# Wall_Power_to__-20.net
KiCad netlist of a schematic drawn in Altium Designer
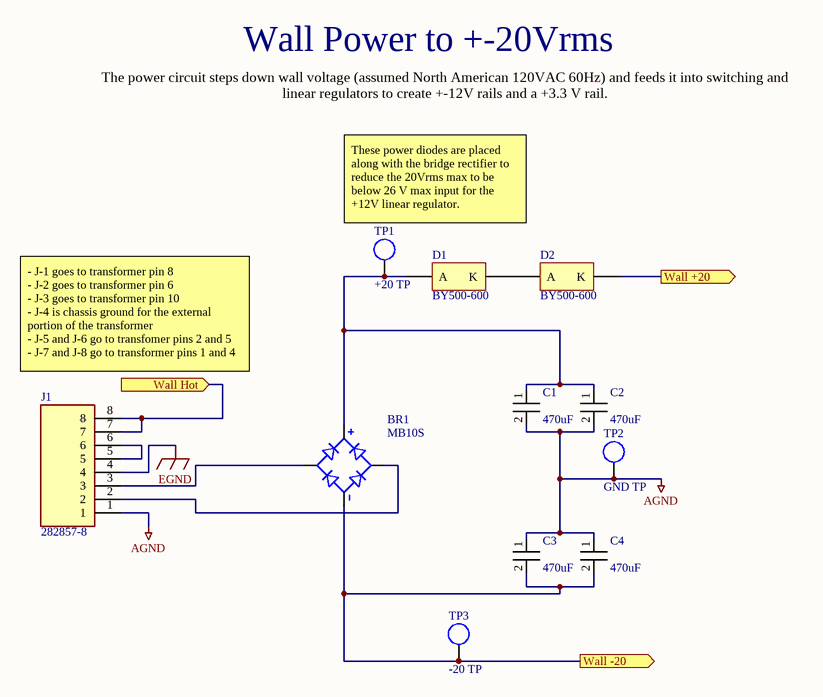
[diagram p0: Wall_Power_to_+-20.SchDoc]

(export (version "E")
  (design (tool "Eeschema 10.0.6"))
  (components
    (comp (ref "BR1")
      (value "MB10S")
      (footprint "SOIC245P670X290-4N")
      (description "Bridge Rectifier Single Phase Standard 1kV Surface Mount 4-SOIC")
      (fields (field (name "DIGI-KEY_PART_NUMBER") "MB10SCT-ND") (field (name "MF") "ON Semiconductor"))
      (libsource (lib "MB10S") (part "MB10S"))
    )
    (comp (ref "C1")
      (value "470uF")
      (footprint "PCBComponent_1")
      (libsource (lib "California Institute of Technology") (part "New symbol 1"))
    )
    (comp (ref "C2")
      (value "470uF")
      (footprint "PCBComponent_1")
      (libsource (lib "California Institute of Technology") (part "New symbol 1"))
    )
    (comp (ref "C3")
      (value "470uF")
      (footprint "PCBComponent_1")
      (libsource (lib "California Institute of Technology") (part "New symbol 1"))
    )
    (comp (ref "C4")
      (value "470uF")
      (footprint "PCBComponent_1")
      (libsource (lib "California Institute of Technology") (part "New symbol 1"))
    )
    (comp (ref "D1")
      (value "BY500-600")
      (footprint "ONSC-AXIAL_LEAD-2-267-05_V")
      (description "Rectifier, 2-Pin Axial_Lead, Pb-Free, Tape and Reel")
      (fields (field (name "MANUFACTURER") "On Semiconductor") (field (name "PARTNUMBER") "1N5822RLG"))
      (libsource (lib "Altium Content Vault") (part "ONSC-D-K1A2-2_A"))
    )
    (comp (ref "D2")
      (value "BY500-600")
      (footprint "ONSC-AXIAL_LEAD-2-267-05_V")
      (description "Rectifier, 2-Pin Axial_Lead, Pb-Free, Tape and Reel")
      (fields (field (name "MANUFACTURER") "On Semiconductor") (field (name "PARTNUMBER") "1N5822RLG"))
      (libsource (lib "Altium Content Vault") (part "ONSC-D-K1A2-2_A"))
    )
    (comp (ref "J1")
      (value "282857-8")
      (footprint "282857-8-Footprint-1")
      (description "Conn Eurostyle Block HDR 8 POS 5.08mm Solder ST Thru-Hole 24A Carton")
      (libsource (lib "California Institute of Technology") (part "282857-8-Symbol-1"))
    )
    (comp (ref "TP1")
      (value "+20 TP")
      (footprint "PCBComponent_1")
      (libsource (lib "test-point") (part "Component_1"))
    )
    (comp (ref "TP2")
      (value "GND TP")
      (footprint "PCBComponent_1")
      (libsource (lib "test-point") (part "Component_1"))
    )
    (comp (ref "TP3")
      (value "-20 TP")
      (footprint "PCBComponent_1")
      (libsource (lib "test-point") (part "Component_1"))
    )
  )
  (nets
    (net (code "1") (name "/Wall +20") (class "Default")
      (node (ref "D2") (pin "1") (pinfunction "K_1") (pintype "passive"))
    )
    (net (code "2") (name "/Wall -20") (class "Default")
      (node (ref "BR1") (pin "2") (pinfunction "NEG_2") (pintype "passive"))
      (node (ref "C3") (pin "2") (pinfunction "-_2") (pintype "passive"))
      (node (ref "C4") (pin "2") (pinfunction "-_2") (pintype "passive"))
      (node (ref "TP3") (pin "TP") (pinfunction "TP_TP") (pintype "passive"))
    )
    (net (code "3") (name "/Wall Hot") (class "Default")
      (node (ref "J1") (pin "7") (pinfunction "7_7") (pintype "passive"))
      (node (ref "J1") (pin "8") (pinfunction "8_8") (pintype "passive"))
    )
    (net (code "4") (name "AGND") (class "Default")
      (node (ref "C1") (pin "2") (pinfunction "-_2") (pintype "passive"))
      (node (ref "C2") (pin "2") (pinfunction "-_2") (pintype "passive"))
      (node (ref "C3") (pin "1") (pinfunction "+_1") (pintype "passive"))
      (node (ref "C4") (pin "1") (pinfunction "+_1") (pintype "passive"))
      (node (ref "J1") (pin "1") (pinfunction "1_1") (pintype "passive"))
      (node (ref "TP2") (pin "TP") (pinfunction "TP_TP") (pintype "passive"))
    )
    (net (code "5") (name "EGND") (class "Default")
      (node (ref "J1") (pin "4") (pinfunction "4_4") (pintype "passive"))
    )
    (net (code "6") (name "Net-(BR1-AC1)") (class "Default")
      (node (ref "BR1") (pin "4") (pinfunction "AC1_4") (pintype "passive"))
      (node (ref "J1") (pin "2") (pinfunction "2_2") (pintype "passive"))
    )
    (net (code "7") (name "Net-(BR1-AC2)") (class "Default")
      (node (ref "BR1") (pin "3") (pinfunction "AC2_3") (pintype "passive"))
      (node (ref "J1") (pin "3") (pinfunction "3_3") (pintype "passive"))
    )
    (net (code "8") (name "Net-(BR1-POS)") (class "Default")
      (node (ref "BR1") (pin "1") (pinfunction "POS_1") (pintype "passive"))
      (node (ref "C1") (pin "1") (pinfunction "+_1") (pintype "passive"))
      (node (ref "C2") (pin "1") (pinfunction "+_1") (pintype "passive"))
      (node (ref "D1") (pin "2") (pinfunction "A_2") (pintype "passive"))
      (node (ref "TP1") (pin "TP") (pinfunction "TP_TP") (pintype "passive"))
    )
    (net (code "9") (name "Net-(D1-K)") (class "Default")
      (node (ref "D1") (pin "1") (pinfunction "K_1") (pintype "passive"))
      (node (ref "D2") (pin "2") (pinfunction "A_2") (pintype "passive"))
    )
    (net (code "10") (name "Net-(J1-Pad5)") (class "Default")
      (node (ref "J1") (pin "5") (pinfunction "5_5") (pintype "passive"))
      (node (ref "J1") (pin "6") (pinfunction "6_6") (pintype "passive"))
    )
  )
)
